# Moisture_8266.net
KiCad netlist of a schematic drawn in EAGLE
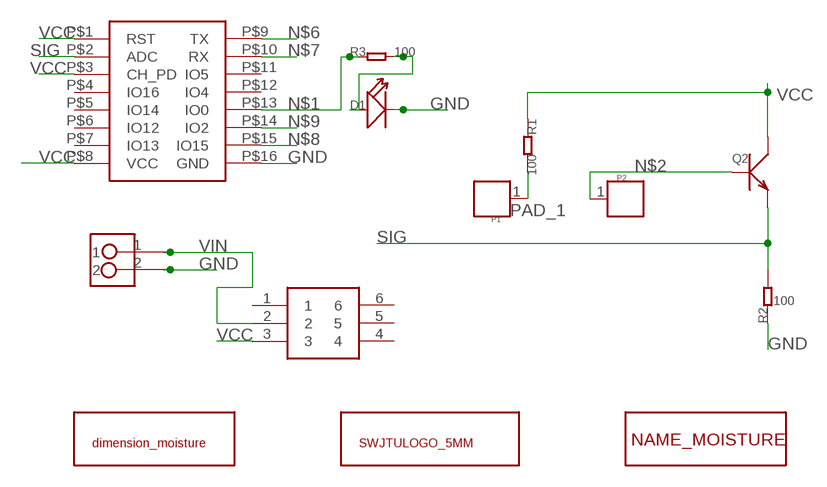
[diagram p0: schematic, sheet 1]

(export (version "E")
  (design (tool "Eeschema 10.0.6"))
  (components
    (comp (ref "D1")
      (value "LED0603")
      (footprint "eagle-import:LED-0603")
      (libsource (lib "eagle-import") (part "LED0603"))
    )
    (comp (ref "P1")
      (value "PAD.03")
      (footprint "eagle-import:1P-SMD-0.76X0.76")
      (libsource (lib "eagle-import") (part "PAD.03"))
    )
    (comp (ref "P2")
      (value "PAD.03")
      (footprint "eagle-import:1P-SMD-0.76X0.76")
      (libsource (lib "eagle-import") (part "PAD.03"))
    )
    (comp (ref "Q2")
      (value "TRANSISTOR-NPN-SOT23''")
      (footprint "eagle-import:SOT23")
      (libsource (lib "eagle-import") (part "TRANSISTOR-NPN-SOT23''"))
    )
    (comp (ref "R1")
      (value "100")
      (footprint "eagle-import:0603")
      (libsource (lib "eagle-import") (part "R-0603"))
    )
    (comp (ref "R2")
      (value "100")
      (footprint "eagle-import:0603")
      (libsource (lib "eagle-import") (part "R-0603"))
    )
    (comp (ref "R3")
      (value "100")
      (footprint "eagle-import:R0603")
      (libsource (lib "eagle-import") (part "Xmaker_R-0603"))
    )
    (comp (ref "U$1")
      (value "MSS-22C02")
      (footprint "eagle-import:MSS-22C02")
      (libsource (lib "eagle-import") (part "MSS-22C02"))
    )
    (comp (ref "U$2")
      (value "SWJTULOGO")
      (footprint "eagle-import:SWJTULOGO10_10MM")
      (libsource (lib "eagle-import") (part "SWJTULOGO"))
    )
    (comp (ref "U$4")
      (value "NAME_MOISTURE")
      (footprint "eagle-import:NAME_MOISTURE")
      (libsource (lib "eagle-import") (part "NAME_MOISTURE"))
    )
    (comp (ref "U$5")
      (value "HEAD_8266_07")
      (footprint "eagle-import:HEAD_8266_07")
      (libsource (lib "eagle-import") (part "HEAD_8266_07"))
    )
    (comp (ref "U$6")
      (value "POWER_3.6V")
      (footprint "eagle-import:POWER_3.6V")
      (libsource (lib "eagle-import") (part "POWER_3.6V"))
    )
    (comp (ref "U$7")
      (value "DIMENSION_MOISTURE_LONG")
      (footprint "eagle-import:MOISTURE_LONG")
      (libsource (lib "eagle-import") (part "DIMENSION_MOISTURE_LONG"))
    )
  )
  (nets
    (net (code "1") (name "/GND") (class "Default")
      (node (ref "D1") (pin "-") (pinfunction "-_-") (pintype "passive"))
      (node (ref "R2") (pin "1") (pinfunction "1_1") (pintype "passive"))
      (node (ref "U$5") (pin "P$16") (pinfunction "GND_P$16") (pintype "bidirectional"))
      (node (ref "U$6") (pin "2") (pinfunction "2_2") (pintype "passive"))
    )
    (net (code "2") (name "/N$1") (class "Default")
      (node (ref "R3") (pin "1") (pinfunction "1_1") (pintype "passive"))
      (node (ref "U$5") (pin "P$13") (pinfunction "IO0_P$13") (pintype "bidirectional"))
    )
    (net (code "3") (name "/N$2") (class "Default")
      (node (ref "P2") (pin "1") (pinfunction "P$1_1") (pintype "bidirectional"))
      (node (ref "Q2") (pin "1") (pinfunction "B_1") (pintype "passive"))
    )
    (net (code "4") (name "/N$6") (class "Default")
      (node (ref "U$5") (pin "P$9") (pinfunction "TX_P$9") (pintype "bidirectional"))
    )
    (net (code "5") (name "/N$7") (class "Default")
      (node (ref "U$5") (pin "P$10") (pinfunction "RX_P$10") (pintype "bidirectional"))
    )
    (net (code "6") (name "/N$8") (class "Default")
      (node (ref "U$5") (pin "P$15") (pinfunction "IO15_P$15") (pintype "bidirectional"))
    )
    (net (code "7") (name "/N$9") (class "Default")
      (node (ref "U$5") (pin "P$14") (pinfunction "IO2_P$14") (pintype "bidirectional"))
    )
    (net (code "8") (name "/PAD_1") (class "Default")
      (node (ref "P1") (pin "1") (pinfunction "P$1_1") (pintype "bidirectional"))
      (node (ref "R1") (pin "2") (pinfunction "2_2") (pintype "passive"))
    )
    (net (code "9") (name "/SIG") (class "Default")
      (node (ref "Q2") (pin "2") (pinfunction "E_2") (pintype "passive"))
      (node (ref "R2") (pin "2") (pinfunction "2_2") (pintype "passive"))
      (node (ref "U$5") (pin "P$2") (pinfunction "ADC_P$2") (pintype "bidirectional"))
    )
    (net (code "10") (name "/VCC") (class "Default")
      (node (ref "Q2") (pin "3") (pinfunction "C_3") (pintype "passive"))
      (node (ref "R1") (pin "1") (pinfunction "1_1") (pintype "passive"))
      (node (ref "U$1") (pin "3") (pinfunction "3_3") (pintype "bidirectional"))
      (node (ref "U$5") (pin "P$1") (pinfunction "RST_P$1") (pintype "bidirectional"))
      (node (ref "U$5") (pin "P$3") (pinfunction "CH_PD_P$3") (pintype "bidirectional"))
      (node (ref "U$5") (pin "P$8") (pinfunction "VCC_P$8") (pintype "bidirectional"))
    )
    (net (code "11") (name "/VIN") (class "Default")
      (node (ref "U$1") (pin "2") (pinfunction "2_2") (pintype "bidirectional"))
      (node (ref "U$6") (pin "1") (pinfunction "1_1") (pintype "passive"))
    )
    (net (code "12") (name "Net-(D1-Pad+)") (class "Default")
      (node (ref "D1") (pin "+") (pinfunction "+_+") (pintype "passive"))
      (node (ref "R3") (pin "2") (pinfunction "2_2") (pintype "passive"))
    )
    (net (code "13") (name "unconnected-(U$1-Pad1)") (class "Default")
      (node (ref "U$1") (pin "1") (pinfunction "1_1") (pintype "bidirectional"))
    )
    (net (code "14") (name "unconnected-(U$1-Pad4)") (class "Default")
      (node (ref "U$1") (pin "4") (pinfunction "4_4") (pintype "bidirectional"))
    )
    (net (code "15") (name "unconnected-(U$1-Pad5)") (class "Default")
      (node (ref "U$1") (pin "5") (pinfunction "5_5") (pintype "bidirectional"))
    )
    (net (code "16") (name "unconnected-(U$1-Pad6)") (class "Default")
      (node (ref "U$1") (pin "6") (pinfunction "6_6") (pintype "bidirectional"))
    )
    (net (code "17") (name "unconnected-(U$5-IO4-PadP$12)") (class "Default")
      (node (ref "U$5") (pin "P$12") (pinfunction "IO4_P$12") (pintype "bidirectional"))
    )
    (net (code "18") (name "unconnected-(U$5-IO5-PadP$11)") (class "Default")
      (node (ref "U$5") (pin "P$11") (pinfunction "IO5_P$11") (pintype "bidirectional"))
    )
    (net (code "19") (name "unconnected-(U$5-IO12-PadP$6)") (class "Default")
      (node (ref "U$5") (pin "P$6") (pinfunction "IO12_P$6") (pintype "bidirectional"))
    )
    (net (code "20") (name "unconnected-(U$5-IO13-PadP$7)") (class "Default")
      (node (ref "U$5") (pin "P$7") (pinfunction "IO13_P$7") (pintype "bidirectional"))
    )
    (net (code "21") (name "unconnected-(U$5-IO14-PadP$5)") (class "Default")
      (node (ref "U$5") (pin "P$5") (pinfunction "IO14_P$5") (pintype "bidirectional"))
    )
    (net (code "22") (name "unconnected-(U$5-IO16-PadP$4)") (class "Default")
      (node (ref "U$5") (pin "P$4") (pinfunction "IO16_P$4") (pintype "bidirectional"))
    )
  )
)
